# LED_Driver.net
KiCad netlist of a schematic drawn in Altium Designer
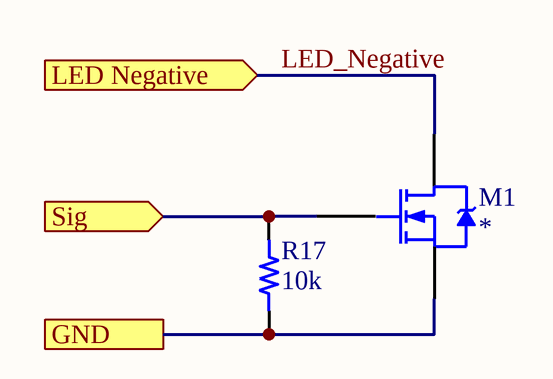
[diagram p0: LED_Driver.SchDoc]

(export (version "E")
  (design (tool "Eeschema 10.0.6"))
  (components
    (comp (ref "M1")
      (value "*")
      (footprint "SOT23-3")
      (description "MOSFET N-CHANNEL 30V 5A SOT23")
      (libsource (lib "altlib") (part "DMG2302UK-7"))
    )
    (comp (ref "R17")
      (value "10k")
      (footprint "RES 0603/1608")
      (fields (field (name "RESISTANCE") "10k"))
      (libsource (lib "altlib") (part "Resistor"))
    )
  )
  (nets
    (net (code "1") (name "/GND") (class "Default")
      (node (ref "M1") (pin "2") (pinfunction "S_2") (pintype "passive"))
      (node (ref "R17") (pin "1") (pinfunction "1_1") (pintype "passive"))
    )
    (net (code "2") (name "/LED_Negative") (class "Default")
      (node (ref "M1") (pin "3") (pinfunction "D_3") (pintype "passive"))
    )
    (net (code "3") (name "/Sig") (class "Default")
      (node (ref "M1") (pin "1") (pinfunction "G_1") (pintype "passive"))
      (node (ref "R17") (pin "2") (pinfunction "2_2") (pintype "passive"))
    )
  )
)
